# ogn_wind_1_4.net
KiCad netlist of a schematic drawn in EAGLE
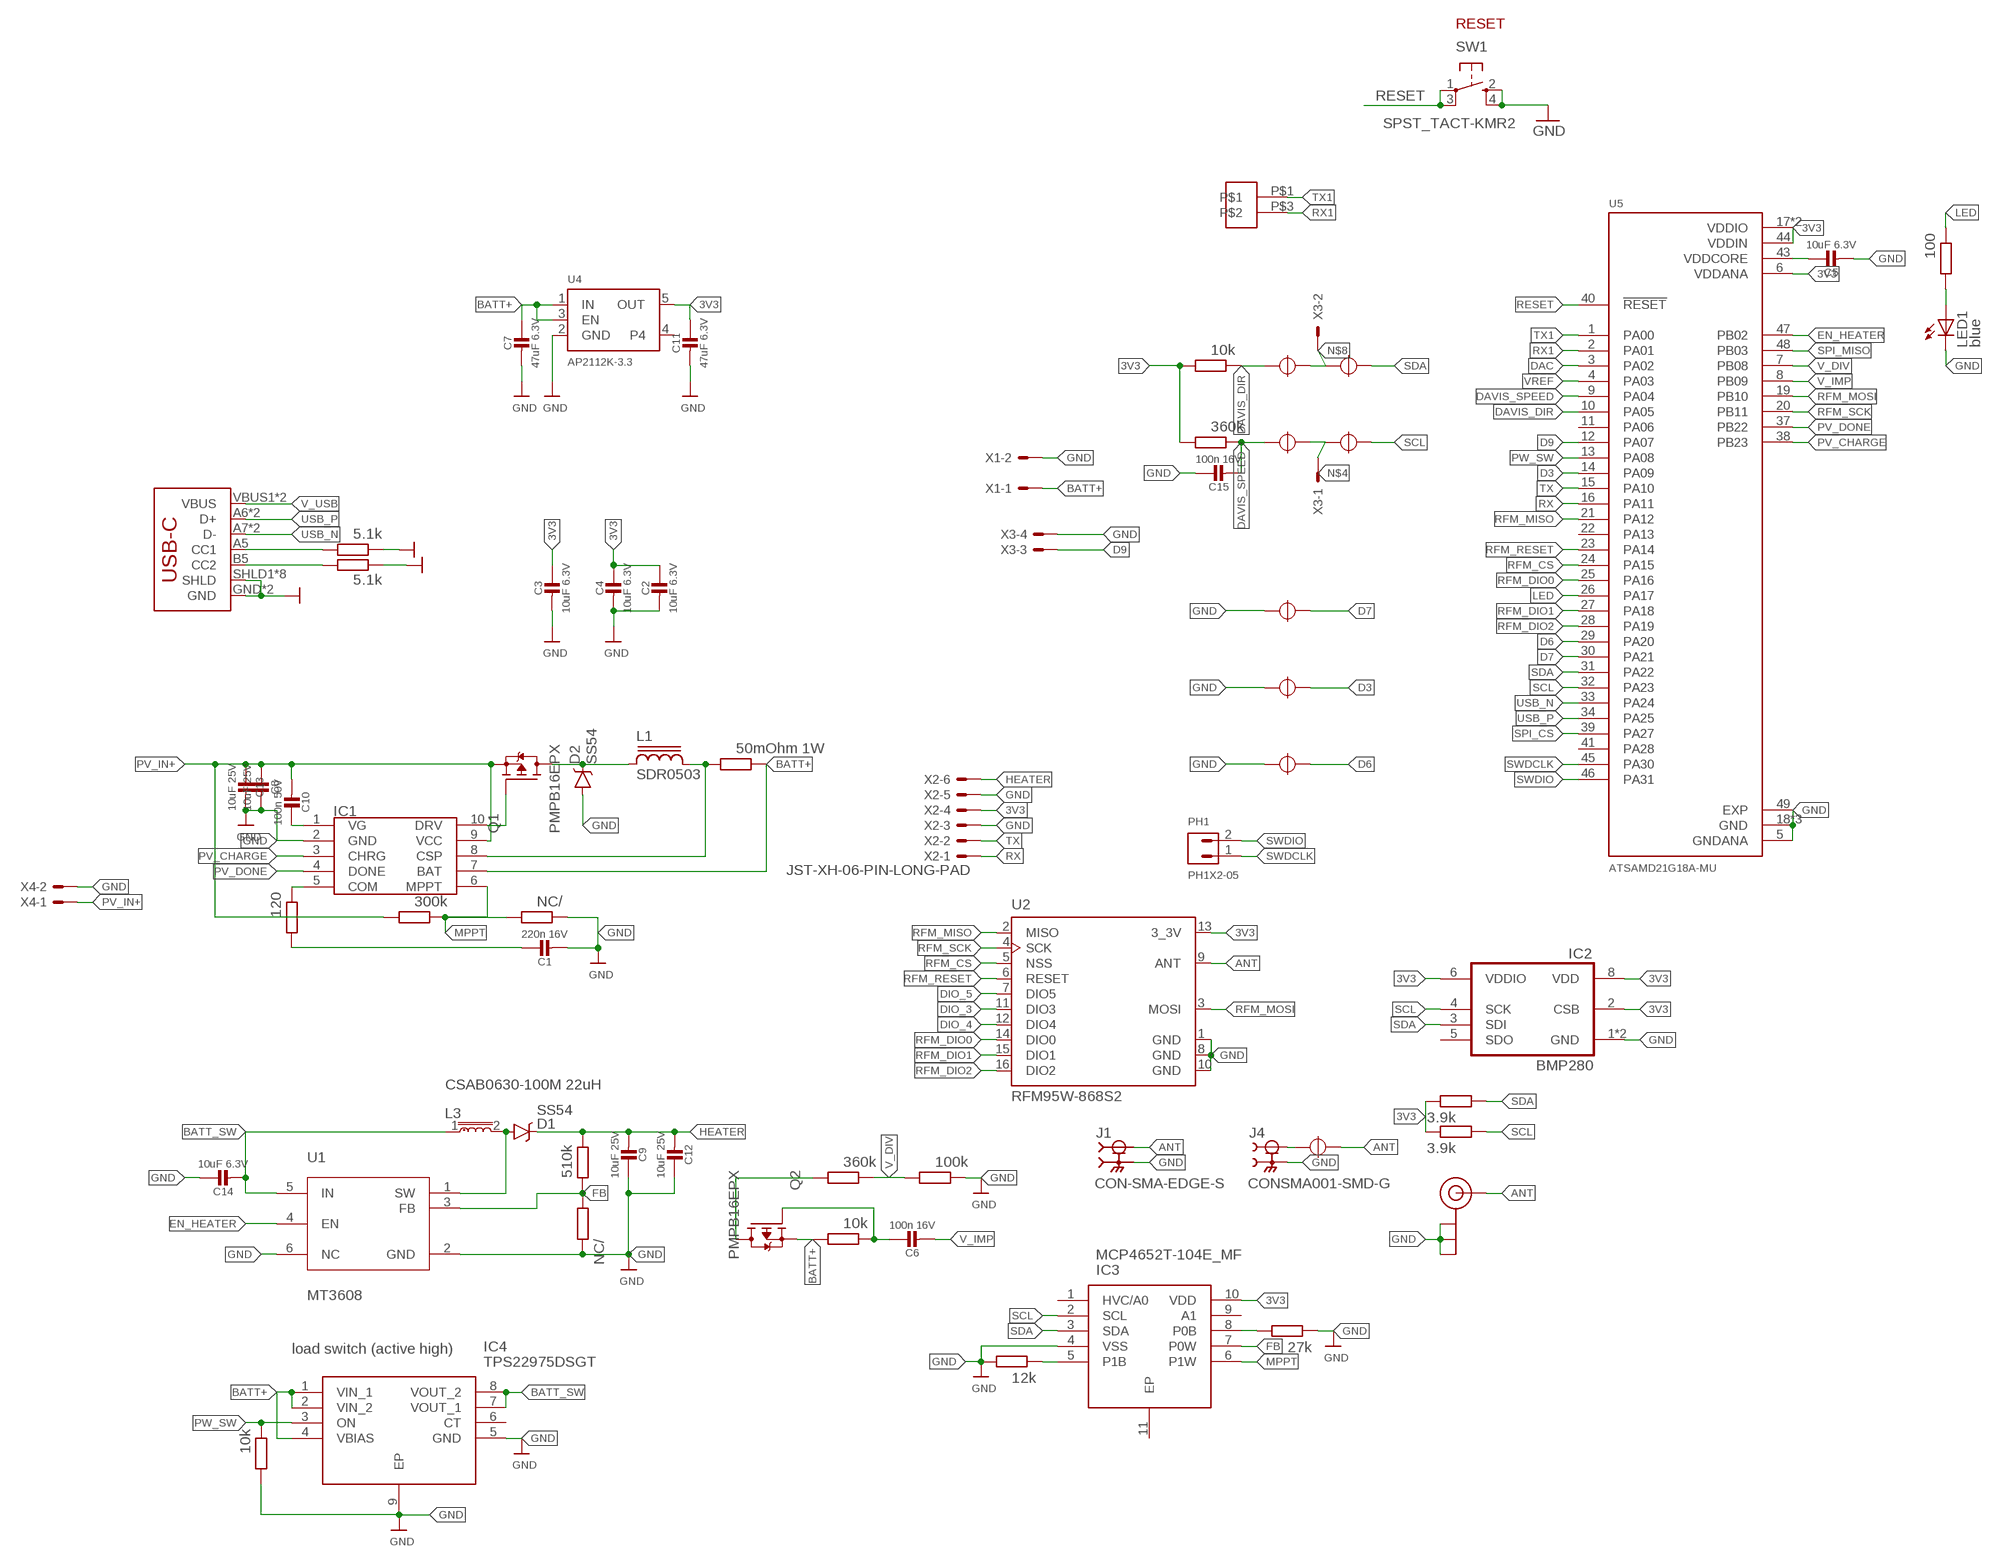
[diagram p0: schematic, sheet 1]

(export (version "E")
  (design (tool "Eeschema 10.0.6"))
  (components
    (comp (ref "ANT_UFL")
      (value "U.FL")
      (footprint "eagle-import:U.FL")
      (libsource (lib "eagle-import") (part "U.FL"))
    )
    (comp (ref "C1")
      (value "220n 16V")
      (footprint "eagle-import:_0402MP")
      (libsource (lib "eagle-import") (part "CAP_CERAMIC_0402MP"))
    )
    (comp (ref "C2")
      (value "10uF 6.3V")
      (footprint "eagle-import:_0402MP")
      (libsource (lib "eagle-import") (part "CAP_CERAMIC_0402MP"))
    )
    (comp (ref "C3")
      (value "10uF 6.3V")
      (footprint "eagle-import:_0402MP")
      (libsource (lib "eagle-import") (part "CAP_CERAMIC_0402MP"))
    )
    (comp (ref "C4")
      (value "10uF 6.3V")
      (footprint "eagle-import:_0402MP")
      (libsource (lib "eagle-import") (part "CAP_CERAMIC_0402MP"))
    )
    (comp (ref "C5")
      (value "10uF 6.3V")
      (footprint "eagle-import:_0402MP")
      (libsource (lib "eagle-import") (part "CAP_CERAMIC_0402MP"))
    )
    (comp (ref "C6")
      (value "100n 16V")
      (footprint "eagle-import:_0402MP")
      (fields (field (name "SPICEPREFIX") "C"))
      (libsource (lib "eagle-import") (part "CAP_CERAMIC_0402MP"))
    )
    (comp (ref "C7")
      (value "47uF 6.3V")
      (footprint "eagle-import:0805-NO")
      (libsource (lib "eagle-import") (part "CAP_CERAMIC0805-NOOUTLINE"))
    )
    (comp (ref "C8")
      (value "10uF 25V")
      (footprint "eagle-import:_0603MP")
      (libsource (lib "eagle-import") (part "CAP_CERAMIC_0603MP"))
    )
    (comp (ref "C9")
      (value "10uF 25V")
      (footprint "eagle-import:_0603MP")
      (libsource (lib "eagle-import") (part "CAP_CERAMIC_0603MP"))
    )
    (comp (ref "C10")
      (value "100n 50V")
      (footprint "eagle-import:_0603MP")
      (libsource (lib "eagle-import") (part "CAP_CERAMIC_0603MP"))
    )
    (comp (ref "C11")
      (value "47uF 6.3V")
      (footprint "eagle-import:0805-NO")
      (libsource (lib "eagle-import") (part "CAP_CERAMIC0805-NOOUTLINE"))
    )
    (comp (ref "C12")
      (value "10uF 25V")
      (footprint "eagle-import:_0603MP")
      (libsource (lib "eagle-import") (part "CAP_CERAMIC_0603MP"))
    )
    (comp (ref "C13")
      (value "10uF 25V")
      (footprint "eagle-import:_0603MP")
      (libsource (lib "eagle-import") (part "CAP_CERAMIC_0603MP"))
    )
    (comp (ref "C14")
      (value "10uF 6.3V")
      (footprint "eagle-import:_0402MP")
      (libsource (lib "eagle-import") (part "CAP_CERAMIC_0402MP"))
    )
    (comp (ref "C15")
      (value "100n 16V")
      (footprint "eagle-import:_0402MP")
      (fields (field (name "SPICEPREFIX") "C"))
      (libsource (lib "eagle-import") (part "CAP_CERAMIC_0402MP"))
    )
    (comp (ref "D1")
      (value "SS54")
      (footprint "eagle-import:DO-214AC")
      (fields (field (name "MF") "MDD"))
      (libsource (lib "eagle-import") (part "SS54"))
    )
    (comp (ref "D2")
      (value "SS54")
      (footprint "eagle-import:DO-214AC")
      (fields (field (name "MF") "MDD"))
      (libsource (lib "eagle-import") (part "SS54"))
    )
    (comp (ref "IC1")
      (value "CN3791")
      (footprint "eagle-import:SSOP10")
      (fields (field (name "MF") "Consonance"))
      (libsource (lib "eagle-import") (part "CN3791"))
    )
    (comp (ref "IC2")
      (value "BMP280")
      (footprint "eagle-import:BMP280")
      (libsource (lib "eagle-import") (part "BMP280"))
    )
    (comp (ref "IC3")
      (value "MCP4652T-104E_MF")
      (footprint "eagle-import:SON50P300X300X100-11N")
      (fields
        (field (name "MANUFACTURER_PART_NUMBER") "MCP4652T-104E/MF")
        (field (name "MOUSER2_PART_NUMBER") "579-MCP4652T-104E/MF")
      )
      (libsource (lib "eagle-import") (part "MCP4652T-104E_MF"))
    )
    (comp (ref "IC4")
      (value "TPS22975DSGT")
      (footprint "eagle-import:SON50P200X200X80-9N")
      (fields (field (name "MF") "Texas Instruments"))
      (libsource (lib "eagle-import") (part "TPS22975DSGT"))
    )
    (comp (ref "J1")
      (value "CON-SMA-EDGE-S")
      (footprint "eagle-import:RFSOLUTIONS_CON-SMA-EDGE-S")
      (fields (field (name "MF") "RF Solutions"))
      (libsource (lib "eagle-import") (part "CON-SMA-EDGE-S"))
    )
    (comp (ref "J2")
      (value "USB_C16PIN")
      (footprint "eagle-import:USB-C-16P")
      (libsource (lib "eagle-import") (part "USB_C16PIN"))
    )
    (comp (ref "J4")
      (value "CONSMA001-SMD-G")
      (footprint "eagle-import:LINX_CONSMA001-SMD-G")
      (fields (field (name "MF") "TE Connectivity"))
      (libsource (lib "eagle-import") (part "CONSMA001-SMD-G"))
    )
    (comp (ref "L1")
      (value "SDR0503")
      (footprint "eagle-import:SDR0503")
      (libsource (lib "eagle-import") (part "SDR0503"))
    )
    (comp (ref "L3")
      (value "CSAB0630-100M 22uH")
      (footprint "eagle-import:INDC6060X300")
      (fields (field (name "MF") "Codaca") (field (name "MP") "CSAB0630-100M"))
      (libsource (lib "eagle-import") (part "CSAB0630-100M"))
    )
    (comp (ref "LED1")
      (value "blue")
      (footprint "eagle-import:CHIPLED_0603")
      (libsource (lib "eagle-import") (part "LEDCHIPLED_0603"))
    )
    (comp (ref "PH1")
      (value "PH1X2-05")
      (footprint "eagle-import:PH005-1-2")
      (libsource (lib "eagle-import") (part "PH1X2-05"))
    )
    (comp (ref "Q1")
      (value "PMPB16EPX")
      (footprint "eagle-import:TRANS_PMPB16EPX")
      (fields (field (name "MF") "Nexperia USA Inc.") (field (name "SPICEPREFIX") "Q"))
      (libsource (lib "eagle-import") (part "PMPB16EPX"))
    )
    (comp (ref "Q2")
      (value "PMPB16EPX")
      (footprint "eagle-import:TRANS_PMPB16EPX")
      (fields (field (name "MF") "Nexperia USA Inc."))
      (libsource (lib "eagle-import") (part "PMPB16EPX"))
    )
    (comp (ref "SW1")
      (value "SPST_TACT-KMR2")
      (footprint "eagle-import:KMR2")
      (libsource (lib "eagle-import") (part "SPST_TACT-KMR2"))
    )
    (comp (ref "U$1") (value "SJ") (footprint "eagle-import:SJ") (libsource (lib "eagle-import") (part "SJ")))
    (comp (ref "U$2") (value "SJ") (footprint "eagle-import:SJ") (libsource (lib "eagle-import") (part "SJ")))
    (comp (ref "U$3") (value "SJ") (footprint "eagle-import:SJ") (libsource (lib "eagle-import") (part "SJ")))
    (comp (ref "U$4") (value "SJ") (footprint "eagle-import:SJ") (libsource (lib "eagle-import") (part "SJ")))
    (comp (ref "U$7") (value "SJ") (footprint "eagle-import:SJ") (libsource (lib "eagle-import") (part "SJ")))
    (comp (ref "U$10")
      (value "SJ")
      (footprint "eagle-import:SJ")
      (libsource (lib "eagle-import") (part "SJ"))
    )
    (comp (ref "U$11")
      (value "SJ")
      (footprint "eagle-import:SJ")
      (libsource (lib "eagle-import") (part "SJ"))
    )
    (comp (ref "U$13")
      (value "SMDPAD2")
      (footprint "eagle-import:SMDPAD2")
      (libsource (lib "eagle-import") (part "SMDPAD2"))
    )
    (comp (ref "U$22")
      (value "SJ")
      (footprint "eagle-import:SJ")
      (libsource (lib "eagle-import") (part "SJ"))
    )
    (comp (ref "U1")
      (value "MT3608")
      (footprint "eagle-import:SOT95P280X145-6N")
      (fields (field (name "MF") "Aerosemi Technology Co., Ltd"))
      (libsource (lib "eagle-import") (part "MT3608"))
    )
    (comp (ref "U2")
      (value "RFM95W-868S2")
      (footprint "eagle-import:XCVR_RFM95W-868S2")
      (fields (field (name "MF") "RF"))
      (libsource (lib "eagle-import") (part "RFM95W-868S2"))
    )
    (comp (ref "U4")
      (value "AP2112K-3.3")
      (footprint "eagle-import:SOT23-5")
      (libsource (lib "eagle-import") (part "VREG_SOT23-5"))
    )
    (comp (ref "U5")
      (value "ATSAMD21G18A-MU")
      (footprint "eagle-import:QFN50P700X700X90-49N")
      (fields (field (name "MF") "Microchip"))
      (libsource (lib "eagle-import") (part "ATSAMD21G18A-MU"))
    )
    (comp (ref "USBCR")
      (value "5.1k")
      (footprint "eagle-import:0402RF")
      (libsource (lib "eagle-import") (part "R-EU_R0402RF"))
    )
    (comp (ref "USBCR1")
      (value "5.1k")
      (footprint "eagle-import:0402RF")
      (libsource (lib "eagle-import") (part "R-EU_R0402RF"))
    )
    (comp (ref "USBCR2")
      (value "360k")
      (footprint "eagle-import:0402RF")
      (fields (field (name "SPICEPREFIX") "B"))
      (libsource (lib "eagle-import") (part "R-EU_R0402RF"))
    )
    (comp (ref "USBCR3")
      (value "100k")
      (footprint "eagle-import:0402RF")
      (fields (field (name "SPICEPREFIX") "B"))
      (libsource (lib "eagle-import") (part "R-EU_R0402RF"))
    )
    (comp (ref "USBCR4")
      (value "10k")
      (footprint "eagle-import:0402RF")
      (fields (field (name "SPICEPREFIX") "B"))
      (libsource (lib "eagle-import") (part "R-EU_R0402RF"))
    )
    (comp (ref "USBCR5")
      (value "10k")
      (footprint "eagle-import:0402RF")
      (libsource (lib "eagle-import") (part "R-EU_R0402RF"))
    )
    (comp (ref "USBCR6")
      (value "300k")
      (footprint "eagle-import:0402RF")
      (libsource (lib "eagle-import") (part "R-EU_R0402RF"))
    )
    (comp (ref "USBCR7")
      (value "NC/")
      (footprint "eagle-import:0402RF")
      (libsource (lib "eagle-import") (part "R-EU_R0402RF"))
    )
    (comp (ref "USBCR8")
      (value "120")
      (footprint "eagle-import:0402RF")
      (libsource (lib "eagle-import") (part "R-EU_R0402RF"))
    )
    (comp (ref "USBCR9")
      (value "510k")
      (footprint "eagle-import:0402RF")
      (libsource (lib "eagle-import") (part "R-EU_R0402RF"))
    )
    (comp (ref "USBCR10")
      (value "NC/")
      (footprint "eagle-import:0402RF")
      (libsource (lib "eagle-import") (part "R-EU_R0402RF"))
    )
    (comp (ref "USBCR11")
      (value "10k")
      (footprint "eagle-import:0402RF")
      (libsource (lib "eagle-import") (part "R-EU_R0402RF"))
    )
    (comp (ref "USBCR12")
      (value "360k")
      (footprint "eagle-import:0402RF")
      (libsource (lib "eagle-import") (part "R-EU_R0402RF"))
    )
    (comp (ref "USBCR13")
      (value "100")
      (footprint "eagle-import:0402RF")
      (libsource (lib "eagle-import") (part "R-EU_R0402RF"))
    )
    (comp (ref "USBCR14")
      (value "3.9k")
      (footprint "eagle-import:0402RF")
      (libsource (lib "eagle-import") (part "R-EU_R0402RF"))
    )
    (comp (ref "USBCR15")
      (value "3.9k")
      (footprint "eagle-import:0402RF")
      (libsource (lib "eagle-import") (part "R-EU_R0402RF"))
    )
    (comp (ref "USBCR17")
      (value "27k")
      (footprint "eagle-import:0402RF")
      (libsource (lib "eagle-import") (part "R-EU_R0402RF"))
    )
    (comp (ref "USBCR18")
      (value "12k")
      (footprint "eagle-import:0402RF")
      (libsource (lib "eagle-import") (part "R-EU_R0402RF"))
    )
    (comp (ref "USBCR19")
      (value "50mOhm 1W")
      (footprint "eagle-import:R1206")
      (libsource (lib "eagle-import") (part "R-EU_R1206"))
    )
    (comp (ref "X1")
      (value "JST-XH-02-PIN-LONG-PAD")
      (footprint "eagle-import:JST-XH-02-PACKAGE-LONG-PAD")
      (libsource (lib "eagle-import") (part "JST-XH-02-PIN-LONG-PAD"))
    )
    (comp (ref "X2")
      (value "JST-XH-06-PIN-LONG-PAD")
      (footprint "eagle-import:JST-XH-06-PACKAGE-LONG-PAD")
      (libsource (lib "eagle-import") (part "JST-XH-06-PIN-LONG-PAD"))
    )
    (comp (ref "X3")
      (value "JST-XH-04-PIN-LONG-PAD")
      (footprint "eagle-import:JST-XH-04-PACKAGE-LONG-PAD")
      (libsource (lib "eagle-import") (part "JST-XH-04-PIN-LONG-PAD"))
    )
    (comp (ref "X4")
      (value "JST-XH-02-PIN-LONG-PAD")
      (footprint "eagle-import:JST-XH-02-PACKAGE-LONG-PAD")
      (libsource (lib "eagle-import") (part "JST-XH-02-PIN-LONG-PAD"))
    )
  )
  (nets
    (net (code "1") (name "3V3") (class "Default")
      (node (ref "C11") (pin "1") (pinfunction "1_1") (pintype "passive"))
      (node (ref "C2") (pin "1") (pinfunction "1_1") (pintype "passive"))
      (node (ref "C3") (pin "1") (pinfunction "1_1") (pintype "passive"))
      (node (ref "C4") (pin "1") (pinfunction "1_1") (pintype "passive"))
      (node (ref "IC2") (pin "2") (pinfunction "CSB_2") (pintype "input"))
      (node (ref "IC2") (pin "6") (pinfunction "VDDIO_6") (pintype "power_in"))
      (node (ref "IC2") (pin "8") (pinfunction "VDD_8") (pintype "power_in"))
      (node (ref "IC3") (pin "10") (pinfunction "VDD_10") (pintype "bidirectional"))
      (node (ref "U2") (pin "13") (pinfunction "3_3V_13") (pintype "power_in"))
      (node (ref "U4") (pin "5") (pinfunction "OUT_5") (pintype "power_in"))
      (node (ref "U5") (pin "17") (pinfunction "VDDIO_17") (pintype "power_in"))
      (node (ref "U5") (pin "36") (pinfunction "VDDIO_36") (pintype "power_in"))
      (node (ref "U5") (pin "44") (pinfunction "VDDIN_44") (pintype "power_in"))
      (node (ref "U5") (pin "6") (pinfunction "VDDANA_6") (pintype "power_in"))
      (node (ref "USBCR11") (pin "1") (pinfunction "1_1") (pintype "passive"))
      (node (ref "USBCR12") (pin "1") (pinfunction "1_1") (pintype "passive"))
      (node (ref "USBCR14") (pin "2") (pinfunction "2_2") (pintype "passive"))
      (node (ref "USBCR15") (pin "2") (pinfunction "2_2") (pintype "passive"))
      (node (ref "X2") (pin "4") (pinfunction "S_4") (pintype "passive"))
    )
    (net (code "2") (name "ANT") (class "Default")
      (node (ref "ANT_UFL") (pin "P$3") (pinfunction "SIGNAL_P$3") (pintype "bidirectional"))
      (node (ref "J1") (pin "1") (pinfunction "1_1") (pintype "passive"))
      (node (ref "U$22") (pin "P$2") (pinfunction "P$2_P$2") (pintype "bidirectional"))
      (node (ref "U2") (pin "9") (pinfunction "ANT_9") (pintype "passive"))
    )
    (net (code "3") (name "BATT+") (class "Default")
      (node (ref "C7") (pin "1") (pinfunction "1_1") (pintype "passive"))
      (node (ref "IC1") (pin "7") (pinfunction "BAT_7") (pintype "bidirectional"))
      (node (ref "IC4") (pin "1") (pinfunction "VIN_1_1") (pintype "bidirectional"))
      (node (ref "IC4") (pin "2") (pinfunction "VIN_2_2") (pintype "bidirectional"))
      (node (ref "IC4") (pin "4") (pinfunction "VBIAS_4") (pintype "bidirectional"))
      (node (ref "Q2") (pin "4") (pinfunction "S_4") (pintype "passive"))
      (node (ref "Q2") (pin "8") (pinfunction "S_8") (pintype "passive"))
      (node (ref "U4") (pin "1") (pinfunction "IN_1") (pintype "power_in"))
      (node (ref "U4") (pin "3") (pinfunction "EN_3") (pintype "input"))
      (node (ref "USBCR19") (pin "2") (pinfunction "2_2") (pintype "passive"))
      (node (ref "USBCR4") (pin "1") (pinfunction "1_1") (pintype "passive"))
      (node (ref "X1") (pin "1") (pinfunction "S_1") (pintype "passive"))
    )
    (net (code "4") (name "BATT_SW") (class "Default")
      (node (ref "C14") (pin "2") (pinfunction "2_2") (pintype "passive"))
      (node (ref "IC4") (pin "7") (pinfunction "VOUT_1_7") (pintype "bidirectional"))
      (node (ref "IC4") (pin "8") (pinfunction "VOUT_2_8") (pintype "bidirectional"))
      (node (ref "L3") (pin "1") (pinfunction "1_1") (pintype "passive"))
      (node (ref "U1") (pin "5") (pinfunction "IN_5") (pintype "input"))
    )
    (net (code "5") (name "D3") (class "Default")
      (node (ref "U$10") (pin "P$2") (pinfunction "P$2_P$2") (pintype "bidirectional"))
      (node (ref "U5") (pin "14") (pinfunction "PA09_14") (pintype "bidirectional"))
    )
    (net (code "6") (name "D6") (class "Default")
      (node (ref "U$11") (pin "P$2") (pinfunction "P$2_P$2") (pintype "bidirectional"))
      (node (ref "U5") (pin "29") (pinfunction "PA20_29") (pintype "bidirectional"))
    )
    (net (code "7") (name "D7") (class "Default")
      (node (ref "U$7") (pin "P$2") (pinfunction "P$2_P$2") (pintype "bidirectional"))
      (node (ref "U5") (pin "30") (pinfunction "PA21_30") (pintype "bidirectional"))
    )
    (net (code "8") (name "D9") (class "Default")
      (node (ref "U5") (pin "12") (pinfunction "PA07_12") (pintype "bidirectional"))
      (node (ref "X3") (pin "3") (pinfunction "S_3") (pintype "passive"))
    )
    (net (code "9") (name "DAC") (class "Default")
      (node (ref "U5") (pin "3") (pinfunction "PA02_3") (pintype "bidirectional"))
    )
    (net (code "10") (name "DAVIS_DIR") (class "Default")
      (node (ref "U$3") (pin "P$1") (pinfunction "P$1_P$1") (pintype "bidirectional"))
      (node (ref "U5") (pin "10") (pinfunction "PA05_10") (pintype "bidirectional"))
      (node (ref "USBCR11") (pin "2") (pinfunction "2_2") (pintype "passive"))
    )
    (net (code "11") (name "DAVIS_SPEED") (class "Default")
      (node (ref "C15") (pin "2") (pinfunction "2_2") (pintype "passive"))
      (node (ref "U$1") (pin "P$1") (pinfunction "P$1_P$1") (pintype "bidirectional"))
      (node (ref "U5") (pin "9") (pinfunction "PA04_9") (pintype "bidirectional"))
      (node (ref "USBCR12") (pin "2") (pinfunction "2_2") (pintype "passive"))
    )
    (net (code "12") (name "DIO_3") (class "Default")
      (node (ref "U2") (pin "11") (pinfunction "DIO3_11") (pintype "bidirectional"))
    )
    (net (code "13") (name "DIO_4") (class "Default")
      (node (ref "U2") (pin "12") (pinfunction "DIO4_12") (pintype "bidirectional"))
    )
    (net (code "14") (name "DIO_5") (class "Default")
      (node (ref "U2") (pin "7") (pinfunction "DIO5_7") (pintype "bidirectional"))
    )
    (net (code "15") (name "EN_HEATER") (class "Default")
      (node (ref "U1") (pin "4") (pinfunction "EN_4") (pintype "input"))
      (node (ref "U5") (pin "47") (pinfunction "PB02_47") (pintype "bidirectional"))
    )
    (net (code "16") (name "FB") (class "Default")
      (node (ref "IC3") (pin "7") (pinfunction "P0W_7") (pintype "bidirectional"))
      (node (ref "U1") (pin "3") (pinfunction "FB_3") (pintype "input"))
      (node (ref "USBCR10") (pin "1") (pinfunction "1_1") (pintype "passive"))
      (node (ref "USBCR9") (pin "1") (pinfunction "1_1") (pintype "passive"))
    )
    (net (code "17") (name "GND") (class "Default")
      (node (ref "ANT_UFL") (pin "P$1") (pinfunction "GND_P$1") (pintype "bidirectional"))
      (node (ref "ANT_UFL") (pin "P$2") (pinfunction "GND_P$2") (pintype "bidirectional"))
      (node (ref "ANT_UFL") (pin "P$4") (pinfunction "GND_P$4") (pintype "bidirectional"))
      (node (ref "C1") (pin "2") (pinfunction "2_2") (pintype "passive"))
      (node (ref "C11") (pin "2") (pinfunction "2_2") (pintype "passive"))
      (node (ref "C12") (pin "1") (pinfunction "1_1") (pintype "passive"))
      (node (ref "C13") (pin "2") (pinfunction "2_2") (pintype "passive"))
      (node (ref "C14") (pin "1") (pinfunction "1_1") (pintype "passive"))
      (node (ref "C15") (pin "1") (pinfunction "1_1") (pintype "passive"))
      (node (ref "C2") (pin "2") (pinfunction "2_2") (pintype "passive"))
      (node (ref "C3") (pin "2") (pinfunction "2_2") (pintype "passive"))
      (node (ref "C4") (pin "2") (pinfunction "2_2") (pintype "passive"))
      (node (ref "C5") (pin "2") (pinfunction "2_2") (pintype "passive"))
      (node (ref "C7") (pin "2") (pinfunction "2_2") (pintype "passive"))
      (node (ref "C8") (pin "2") (pinfunction "2_2") (pintype "passive"))
      (node (ref "C9") (pin "1") (pinfunction "1_1") (pintype "passive"))
      (node (ref "D2") (pin "A") (pinfunction "A_A") (pintype "passive"))
      (node (ref "IC1") (pin "2") (pinfunction "GND_2") (pintype "bidirectional"))
      (node (ref "IC2") (pin "1") (pinfunction "GND_1") (pintype "power_in"))
      (node (ref "IC2") (pin "7") (pinfunction "GND_7") (pintype "power_in"))
      (node (ref "IC3") (pin "4") (pinfunction "VSS_4") (pintype "bidirectional"))
      (node (ref "IC4") (pin "5") (pinfunction "GND_5") (pintype "bidirectional"))
      (node (ref "IC4") (pin "9") (pinfunction "EP_9") (pintype "bidirectional"))
      (node (ref "J1") (pin "G1") (pinfunction "2_G1") (pintype "passive"))
      (node (ref "J1") (pin "G2") (pinfunction "2_G2") (pintype "passive"))
      (node (ref "J1") (pin "G3") (pinfunction "2_G3") (pintype "passive"))
      (node (ref "J1") (pin "G4") (pinfunction "2_G4") (pintype "passive"))
      (node (ref "J2") (pin "GND") (pinfunction "GND_GND") (pintype "bidirectional"))
      (node (ref "J2") (pin "GND2") (pinfunction "GND_GND2") (pintype "bidirectional"))
      (node (ref "J2") (pin "SHLD1") (pinfunction "SHLD_SHLD1") (pintype "bidirectional"))
      (node (ref "J2") (pin "SHLD2") (pinfunction "SHLD_SHLD2") (pintype "bidirectional"))
      (node (ref "J2") (pin "SHLD3") (pinfunction "SHLD_SHLD3") (pintype "bidirectional"))
      (node (ref "J2") (pin "SHLD4") (pinfunction "SHLD_SHLD4") (pintype "bidirectional"))
      (node (ref "J2") (pin "SHLD5") (pinfunction "SHLD_SHLD5") (pintype "bidirectional"))
      (node (ref "J2") (pin "SHLD6") (pinfunction "SHLD_SHLD6") (pintype "bidirectional"))
      (node (ref "J2") (pin "SHLD7") (pinfunction "SHLD_SHLD7") (pintype "bidirectional"))
      (node (ref "J2") (pin "SHLD8") (pinfunction "SHLD_SHLD8") (pintype "bidirectional"))
      (node (ref "J4") (pin "S1") (pinfunction "2_S1") (pintype "passive"))
      (node (ref "J4") (pin "S2") (pinfunction "2_S2") (pintype "passive"))
      (node (ref "LED1") (pin "C") (pinfunction "C_C") (pintype "passive"))
      (node (ref "SW1") (pin "2") (pinfunction "S_2") (pintype "passive"))
      (node (ref "SW1") (pin "4") (pinfunction "S1_4") (pintype "passive"))
      (node (ref "U$10") (pin "P$1") (pinfunction "P$1_P$1") (pintype "bidirectional"))
      (node (ref "U$11") (pin "P$1") (pinfunction "P$1_P$1") (pintype "bidirectional"))
      (node (ref "U$7") (pin "P$1") (pinfunction "P$1_P$1") (pintype "bidirectional"))
      (node (ref "U1") (pin "2") (pinfunction "GND_2") (pintype "power_in"))
      (node (ref "U1") (pin "6") (pinfunction "NC_6") (pintype "bidirectional"))
      (node (ref "U2") (pin "1") (pinfunction "GND_1") (pintype "power_in"))
      (node (ref "U2") (pin "10") (pinfunction "GND_10") (pintype "power_in"))
      (node (ref "U2") (pin "8") (pinfunction "GND_8") (pintype "power_in"))
      (node (ref "U4") (pin "2") (pinfunction "GND_2") (pintype "power_in"))
      (node (ref "U5") (pin "18") (pinfunction "GND_18") (pintype "power_in"))
      (node (ref "U5") (pin "35") (pinfunction "GND_35") (pintype "power_in"))
      (node (ref "U5") (pin "42") (pinfunction "GND_42") (pintype "power_in"))
      (node (ref "U5") (pin "49") (pinfunction "EXP_49") (pintype "power_in"))
      (node (ref "U5") (pin "5") (pinfunction "GNDANA_5") (pintype "power_in"))
      (node (ref "USBCR") (pin "2") (pinfunction "2_2") (pintype "passive"))
      (node (ref "USBCR1") (pin "2") (pinfunction "2_2") (pintype "passive"))
      (node (ref "USBCR10") (pin "2") (pinfunction "2_2") (pintype "passive"))
      (node (ref "USBCR17") (pin "2") (pinfunction "2_2") (pintype "passive"))
      (node (ref "USBCR18") (pin "1") (pinfunction "1_1") (pintype "passive"))
      (node (ref "USBCR3") (pin "2") (pinfunction "2_2") (pintype "passive"))
      (node (ref "USBCR5") (pin "1") (pinfunction "1_1") (pintype "passive"))
      (node (ref "USBCR7") (pin "2") (pinfunction "2_2") (pintype "passive"))
      (node (ref "X1") (pin "2") (pinfunction "S_2") (pintype "passive"))
      (node (ref "X2") (pin "3") (pinfunction "S_3") (pintype "passive"))
      (node (ref "X2") (pin "5") (pinfunction "S_5") (pintype "passive"))
      (node (ref "X3") (pin "4") (pinfunction "S_4") (pintype "passive"))
      (node (ref "X4") (pin "2") (pinfunction "S_2") (pintype "passive"))
    )
    (net (code "18") (name "HEATER") (class "Default")
      (node (ref "C12") (pin "2") (pinfunction "2_2") (pintype "passive"))
      (node (ref "C9") (pin "2") (pinfunction "2_2") (pintype "passive"))
      (node (ref "D1") (pin "C") (pinfunction "C_C") (pintype "passive"))
      (node (ref "USBCR9") (pin "2") (pinfunction "2_2") (pintype "passive"))
      (node (ref "X2") (pin "6") (pinfunction "S_6") (pintype "passive"))
    )
    (net (code "19") (name "LED") (class "Default")
      (node (ref "U5") (pin "26") (pinfunction "PA17_26") (pintype "bidirectional"))
      (node (ref "USBCR13") (pin "2") (pinfunction "2_2") (pintype "passive"))
    )
    (net (code "20") (name "MPPT") (class "Default")
      (node (ref "IC1") (pin "6") (pinfunction "MPPT_6") (pintype "bidirectional"))
      (node (ref "IC3") (pin "6") (pinfunction "P1W_6") (pintype "bidirectional"))
      (node (ref "USBCR6") (pin "2") (pinfunction "2_2") (pintype "passive"))
      (node (ref "USBCR7") (pin "1") (pinfunction "1_1") (pintype "passive"))
    )
    (net (code "21") (name "N$4") (class "Default")
      (node (ref "U$1") (pin "P$2") (pinfunction "P$2_P$2") (pintype "bidirectional"))
      (node (ref "U$2") (pin "P$1") (pinfunction "P$1_P$1") (pintype "bidirectional"))
      (node (ref "X3") (pin "1") (pinfunction "S_1") (pintype "passive"))
    )
    (net (code "22") (name "N$8") (class "Default")
      (node (ref "U$3") (pin "P$2") (pinfunction "P$2_P$2") (pintype "bidirectional"))
      (node (ref "U$4") (pin "P$1") (pinfunction "P$1_P$1") (pintype "bidirectional"))
      (node (ref "X3") (pin "2") (pinfunction "S_2") (pintype "passive"))
    )
    (net (code "23") (name "Net-(C1-Pad1)") (class "Default")
      (node (ref "C1") (pin "1") (pinfunction "1_1") (pintype "passive"))
      (node (ref "USBCR8") (pin "1") (pinfunction "1_1") (pintype "passive"))
    )
    (net (code "24") (name "Net-(D2-PadC)") (class "Default")
      (node (ref "D2") (pin "C") (pinfunction "C_C") (pintype "passive"))
      (node (ref "L1") (pin "1") (pinfunction "1_1") (pintype "passive"))
      (node (ref "Q1") (pin "1") (pinfunction "D_1") (pintype "passive"))
      (node (ref "Q1") (pin "2") (pinfunction "D_2") (pintype "passive"))
      (node (ref "Q1") (pin "5") (pinfunction "D_5") (pintype "passive"))
      (node (ref "Q1") (pin "6") (pinfunction "D_6") (pintype "passive"))
      (node (ref "Q1") (pin "7") (pinfunction "D_7") (pintype "passive"))
    )
    (net (code "25") (name "Net-(IC1-COM)") (class "Default")
      (node (ref "IC1") (pin "5") (pinfunction "COM_5") (pintype "bidirectional"))
      (node (ref "USBCR8") (pin "2") (pinfunction "2_2") (pintype "passive"))
    )
    (net (code "26") (name "Net-(IC1-CSP)") (class "Default")
      (node (ref "IC1") (pin "8") (pinfunction "CSP_8") (pintype "bidirectional"))
      (node (ref "L1") (pin "2") (pinfunction "2_2") (pintype "passive"))
      (node (ref "USBCR19") (pin "1") (pinfunction "1_1") (pintype "passive"))
    )
    (net (code "27") (name "Net-(IC1-DRV)") (class "Default")
      (node (ref "IC1") (pin "10") (pinfunction "DRV_10") (pintype "bidirectional"))
      (node (ref "Q1") (pin "3") (pinfunction "G_3") (pintype "passive"))
    )
    (net (code "28") (name "Net-(IC1-VG)") (class "Default")
      (node (ref "C10") (pin "1") (pinfunction "1_1") (pintype "passive"))
      (node (ref "IC1") (pin "1") (pinfunction "VG_1") (pintype "bidirectional"))
    )
    (net (code "29") (name "Net-(IC3-P0B)") (class "Default")
      (node (ref "IC3") (pin "8") (pinfunction "P0B_8") (pintype "bidirectional"))
      (node (ref "USBCR17") (pin "1") (pinfunction "1_1") (pintype "passive"))
    )
    (net (code "30") (name "Net-(IC3-P1B)") (class "Default")
      (node (ref "IC3") (pin "5") (pinfunction "P1B_5") (pintype "bidirectional"))
      (node (ref "USBCR18") (pin "2") (pinfunction "2_2") (pintype "passive"))
    )
    (net (code "31") (name "Net-(J2-CC1)") (class "Default")
      (node (ref "J2") (pin "A5") (pinfunction "CC1_A5") (pintype "bidirectional"))
      (node (ref "USBCR") (pin "1") (pinfunction "1_1") (pintype "passive"))
    )
    (net (code "32") (name "Net-(J2-CC2)") (class "Default")
      (node (ref "J2") (pin "B5") (pinfunction "CC2_B5") (pintype "bidirectional"))
      (node (ref "USBCR1") (pin "1") (pinfunction "1_1") (pintype "passive"))
    )
    (net (code "33") (name "Net-(J4-Pad1)") (class "Default")
      (node (ref "J4") (pin "1") (pinfunction "1_1") (pintype "passive"))
      (node (ref "U$22") (pin "P$1") (pinfunction "P$1_P$1") (pintype "bidirectional"))
    )
    (net (code "34") (name "Net-(LED1-PadA)") (class "Default")
      (node (ref "LED1") (pin "A") (pinfunction "A_A") (pintype "passive"))
      (node (ref "USBCR13") (pin "1") (pinfunction "1_1") (pintype "passive"))
    )
    (net (code "35") (name "Net-(Q2-D-Pad1)") (class "Default")
      (node (ref "Q2") (pin "1") (pinfunction "D_1") (pintype "passive"))
      (node (ref "Q2") (pin "2") (pinfunction "D_2") (pintype "passive"))
      (node (ref "Q2") (pin "5") (pinfunction "D_5") (pintype "passive"))
      (node (ref "Q2") (pin "6") (pinfunction "D_6") (pintype "passive"))
      (node (ref "Q2") (pin "7") (pinfunction "D_7") (pintype "passive"))
      (node (ref "USBCR2") (pin "1") (pinfunction "1_1") (pintype "passive"))
    )
    (net (code "36") (name "Net-(Q2-G)") (class "Default")
      (node (ref "C6") (pin "1") (pinfunction "1_1") (pintype "passive"))
      (node (ref "Q2") (pin "3") (pinfunction "G_3") (pintype "passive"))
      (node (ref "USBCR4") (pin "2") (pinfunction "2_2") (pintype "passive"))
    )
    (net (code "37") (name "Net-(U1-SW)") (class "Default")
      (node (ref "D1") (pin "A") (pinfunction "A_A") (pintype "passive"))
      (node (ref "L3") (pin "2") (pinfunction "2_2") (pintype "passive"))
      (node (ref "U1") (pin "1") (pinfunction "SW_1") (pintype "output"))
    )
    (net (code "38") (name "Net-(U5-VDDCORE)") (class "Default")
      (node (ref "C5") (pin "1") (pinfunction "1_1") (pintype "passive"))
      (node (ref "U5") (pin "43") (pinfunction "VDDCORE_43") (pintype "power_in"))
    )
    (net (code "39") (name "PV_CHARGE") (class "Default")
      (node (ref "IC1") (pin "3") (pinfunction "CHRG_3") (pintype "bidirectional"))
      (node (ref "U5") (pin "38") (pinfunction "PB23_38") (pintype "bidirectional"))
    )
    (net (code "40") (name "PV_DONE") (class "Default")
      (node (ref "IC1") (pin "4") (pinfunction "DONE_4") (pintype "bidirectional"))
      (node (ref "U5") (pin "37") (pinfunction "PB22_37") (pintype "bidirectional"))
    )
    (net (code "41") (name "PV_IN+") (class "Default")
      (node (ref "C10") (pin "2") (pinfunction "2_2") (pintype "passive"))
      (node (ref "C13") (pin "1") (pinfunction "1_1") (pintype "passive"))
      (node (ref "C8") (pin "1") (pinfunction "1_1") (pintype "passive"))
      (node (ref "IC1") (pin "9") (pinfunction "VCC_9") (pintype "bidirectional"))
      (node (ref "Q1") (pin "4") (pinfunction "S_4") (pintype "passive"))
      (node (ref "Q1") (pin "8") (pinfunction "S_8") (pintype "passive"))
      (node (ref "USBCR6") (pin "1") (pinfunction "1_1") (pintype "passive"))
      (node (ref "X4") (pin "1") (pinfunction "S_1") (pintype "passive"))
    )
    (net (code "42") (name "PW_SW") (class "Default")
      (node (ref "IC4") (pin "3") (pinfunction "ON_3") (pintype "bidirectional"))
      (node (ref "U5") (pin "13") (pinfunction "PA08_13") (pintype "bidirectional"))
      (node (ref "USBCR5") (pin "2") (pinfunction "2_2") (pintype "passive"))
    )
    (net (code "43") (name "RESET") (class "Default")
      (node (ref "SW1") (pin "1") (pinfunction "P_1") (pintype "passive"))
      (node (ref "SW1") (pin "3") (pinfunction "P1_3") (pintype "passive"))
      (node (ref "U5") (pin "40") (pinfunction "~{RESET}_40") (pintype "input"))
    )
    (net (code "44") (name "RFM_CS") (class "Default")
      (node (ref "U2") (pin "5") (pinfunction "NSS_5") (pintype "input"))
      (node (ref "U5") (pin "24") (pinfunction "PA15_24") (pintype "bidirectional"))
    )
    (net (code "45") (name "RFM_DIO0") (class "Default")
      (node (ref "U2") (pin "14") (pinfunction "DIO0_14") (pintype "bidirectional"))
      (node (ref "U5") (pin "25") (pinfunction "PA16_25") (pintype "bidirectional"))
    )
    (net (code "46") (name "RFM_DIO1") (class "Default")
      (node (ref "U2") (pin "15") (pinfunction "DIO1_15") (pintype "bidirectional"))
      (node (ref "U5") (pin "27") (pinfunction "PA18_27") (pintype "bidirectional"))
    )
    (net (code "47") (name "RFM_DIO2") (class "Default")
      (node (ref "U2") (pin "16") (pinfunction "DIO2_16") (pintype "bidirectional"))
      (node (ref "U5") (pin "28") (pinfunction "PA19_28") (pintype "bidirectional"))
    )
    (net (code "48") (name "RFM_MISO") (class "Default")
      (node (ref "U2") (pin "2") (pinfunction "MISO_2") (pintype "input"))
      (node (ref "U5") (pin "21") (pinfunction "PA12_21") (pintype "bidirectional"))
    )
    (net (code "49") (name "RFM_MOSI") (class "Default")
      (node (ref "U2") (pin "3") (pinfunction "MOSI_3") (pintype "output"))
      (node (ref "U5") (pin "19") (pinfunction "PB10_19") (pintype "bidirectional"))
    )
    (net (code "50") (name "RFM_RESET") (class "Default")
      (node (ref "U2") (pin "6") (pinfunction "RESET_6") (pintype "bidirectional"))
      (node (ref "U5") (pin "23") (pinfunction "PA14_23") (pintype "bidirectional"))
    )
    (net (code "51") (name "RFM_SCK") (class "Default")
      (node (ref "U2") (pin "4") (pinfunction "SCK_4") (pintype "input"))
      (node (ref "U5") (pin "20") (pinfunction "PB11_20") (pintype "bidirectional"))
    )
    (net (code "52") (name "RX") (class "Default")
      (node (ref "U5") (pin "16") (pinfunction "PA11_16") (pintype "bidirectional"))
      (node (ref "X2") (pin "1") (pinfunction "S_1") (pintype "passive"))
    )
    (net (code "53") (name "RX1") (class "Default")
      (node (ref "U$13") (pin "P$3") (pinfunction "P$2_P$3") (pintype "bidirectional"))
      (node (ref "U5") (pin "2") (pinfunction "PA01_2") (pintype "bidirectional"))
    )
    (net (code "54") (name "SCL") (class "Default")
      (node (ref "IC2") (pin "4") (pinfunction "SCK_4") (pintype "bidirectional"))
      (node (ref "IC3") (pin "2") (pinfunction "SCL_2") (pintype "bidirectional"))
      (node (ref "U$2") (pin "P$2") (pinfunction "P$2_P$2") (pintype "bidirectional"))
      (node (ref "U5") (pin "32") (pinfunction "PA23_32") (pintype "bidirectional"))
      (node (ref "USBCR15") (pin "1") (pinfunction "1_1") (pintype "passive"))
    )
    (net (code "55") (name "SDA") (class "Default")
      (node (ref "IC2") (pin "3") (pinfunction "SDI_3") (pintype "bidirectional"))
      (node (ref "IC3") (pin "3") (pinfunction "SDA_3") (pintype "bidirectional"))
      (node (ref "U$4") (pin "P$2") (pinfunction "P$2_P$2") (pintype "bidirectional"))
      (node (ref "U5") (pin "31") (pinfunction "PA22_31") (pintype "bidirectional"))
      (node (ref "USBCR14") (pin "1") (pinfunction "1_1") (pintype "passive"))
    )
    (net (code "56") (name "SPI_CS") (class "Default")
      (node (ref "U5") (pin "39") (pinfunction "PA27_39") (pintype "bidirectional"))
    )
    (net (code "57") (name "SPI_MISO") (class "Default")
      (node (ref "U5") (pin "48") (pinfunction "PB03_48") (pintype "bidirectional"))
    )
    (net (code "58") (name "SWDCLK") (class "Default")
      (node (ref "PH1") (pin "1") (pinfunction "1_1") (pintype "bidirectional"))
      (node (ref "U5") (pin "45") (pinfunction "PA30_45") (pintype "bidirectional"))
    )
    (net (code "59") (name "SWDIO") (class "Default")
      (node (ref "PH1") (pin "2") (pinfunction "2_2") (pintype "bidirectional"))
      (node (ref "U5") (pin "46") (pinfunction "PA31_46") (pintype "bidirectional"))
    )
    (net (code "60") (name "TX") (class "Default")
      (node (ref "U5") (pin "15") (pinfunction "PA10_15") (pintype "bidirectional"))
      (node (ref "X2") (pin "2") (pinfunction "S_2") (pintype "passive"))
    )
    (net (code "61") (name "TX1") (class "Default")
      (node (ref "U$13") (pin "P$1") (pinfunction "P$1_P$1") (pintype "bidirectional"))
      (node (ref "U5") (pin "1") (pinfunction "PA00_1") (pintype "bidirectional"))
    )
    (net (code "62") (name "USB_N") (class "Default")
      (node (ref "J2") (pin "A7") (pinfunction "D-_A7") (pintype "bidirectional"))
      (node (ref "J2") (pin "B7") (pinfunction "D-_B7") (pintype "bidirectional"))
      (node (ref "U5") (pin "33") (pinfunction "PA24_33") (pintype "bidirectional"))
    )
    (net (code "63") (name "USB_P") (class "Default")
      (node (ref "J2") (pin "A6") (pinfunction "D+_A6") (pintype "bidirectional"))
      (node (ref "J2") (pin "B6") (pinfunction "D+_B6") (pintype "bidirectional"))
      (node (ref "U5") (pin "34") (pinfunction "PA25_34") (pintype "bidirectional"))
    )
    (net (code "64") (name "VREF") (class "Default")
      (node (ref "U5") (pin "4") (pinfunction "PA03_4") (pintype "bidirectional"))
    )
    (net (code "65") (name "V_DIV") (class "Default")
      (node (ref "U5") (pin "7") (pinfunction "PB08_7") (pintype "bidirectional"))
      (node (ref "USBCR2") (pin "2") (pinfunction "2_2") (pintype "passive"))
      (node (ref "USBCR3") (pin "1") (pinfunction "1_1") (pintype "passive"))
    )
    (net (code "66") (name "V_IMP") (class "Default")
      (node (ref "C6") (pin "2") (pinfunction "2_2") (pintype "passive"))
      (node (ref "U5") (pin "8") (pinfunction "PB09_8") (pintype "bidirectional"))
    )
    (net (code "67") (name "V_USB") (class "Default")
      (node (ref "J2") (pin "VBUS1") (pinfunction "VBUS_VBUS1") (pintype "bidirectional"))
      (node (ref "J2") (pin "VBUS2") (pinfunction "VBUS_VBUS2") (pintype "bidirectional"))
    )
    (net (code "68") (name "unconnected-(IC2-SDO-Pad5)") (class "Default")
      (node (ref "IC2") (pin "5") (pinfunction "SDO_5") (pintype "input"))
    )
    (net (code "69") (name "unconnected-(IC3-A1-Pad9)") (class "Default")
      (node (ref "IC3") (pin "9") (pinfunction "A1_9") (pintype "bidirectional"))
    )
    (net (code "70") (name "unconnected-(IC3-EP-Pad11)") (class "Default")
      (node (ref "IC3") (pin "11") (pinfunction "EP_11") (pintype "bidirectional"))
    )
    (net (code "71") (name "unconnected-(IC3-HVC{slash}A0-Pad1)") (class "Default")
      (node (ref "IC3") (pin "1") (pinfunction "HVC/A0_1") (pintype "bidirectional"))
    )
    (net (code "72") (name "unconnected-(IC4-CT-Pad6)") (class "Default")
      (node (ref "IC4") (pin "6") (pinfunction "CT_6") (pintype "bidirectional"))
    )
    (net (code "73") (name "unconnected-(U4-P4-Pad4)") (class "Default")
      (node (ref "U4") (pin "4") (pinfunction "P4_4") (pintype "bidirectional"))
    )
    (net (code "74") (name "unconnected-(U5-PA06-Pad11)") (class "Default")
      (node (ref "U5") (pin "11") (pinfunction "PA06_11") (pintype "bidirectional"))
    )
    (net (code "75") (name "unconnected-(U5-PA13-Pad22)") (class "Default")
      (node (ref "U5") (pin "22") (pinfunction "PA13_22") (pintype "bidirectional"))
    )
    (net (code "76") (name "unconnected-(U5-PA28-Pad41)") (class "Default")
      (node (ref "U5") (pin "41") (pinfunction "PA28_41") (pintype "bidirectional"))
    )
  )
)
